# bridge.net
KiCad netlist of a schematic drawn in EAGLE
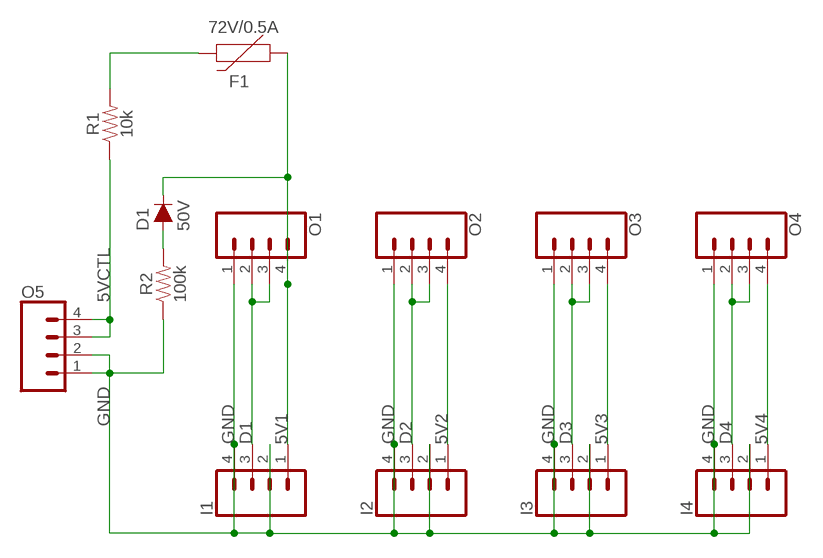
[diagram p0: schematic, sheet 1]

(export (version "E")
  (design (tool "Eeschema 10.0.6"))
  (components
    (comp (ref "D1")
      (value "50V")
      (footprint "eagle-import:DIODE-1N4001")
      (libsource (lib "eagle-import") (part "DIODE-PTH"))
    )
    (comp (ref "F1")
      (value "72V/0.5A")
      (footprint "eagle-import:PTH")
      (libsource (lib "eagle-import") (part "PPTC_PTH"))
    )
    (comp (ref "I1")
      (value "CONN_04SCREW")
      (footprint "eagle-import:SCREWTERMINAL-3.5MM-4")
      (libsource (lib "eagle-import") (part "CONN_04SCREW"))
    )
    (comp (ref "I2")
      (value "CONN_04SCREW")
      (footprint "eagle-import:SCREWTERMINAL-3.5MM-4")
      (libsource (lib "eagle-import") (part "CONN_04SCREW"))
    )
    (comp (ref "I3")
      (value "CONN_04SCREW")
      (footprint "eagle-import:SCREWTERMINAL-3.5MM-4")
      (libsource (lib "eagle-import") (part "CONN_04SCREW"))
    )
    (comp (ref "I4")
      (value "CONN_04SCREW")
      (footprint "eagle-import:SCREWTERMINAL-3.5MM-4")
      (libsource (lib "eagle-import") (part "CONN_04SCREW"))
    )
    (comp (ref "O1")
      (value "CONN_04SCREW")
      (footprint "eagle-import:SCREWTERMINAL-3.5MM-4")
      (libsource (lib "eagle-import") (part "CONN_04SCREW"))
    )
    (comp (ref "O2")
      (value "CONN_04SCREW")
      (footprint "eagle-import:SCREWTERMINAL-3.5MM-4")
      (libsource (lib "eagle-import") (part "CONN_04SCREW"))
    )
    (comp (ref "O3")
      (value "CONN_04SCREW")
      (footprint "eagle-import:SCREWTERMINAL-3.5MM-4")
      (libsource (lib "eagle-import") (part "CONN_04SCREW"))
    )
    (comp (ref "O4")
      (value "CONN_04SCREW")
      (footprint "eagle-import:SCREWTERMINAL-3.5MM-4")
      (libsource (lib "eagle-import") (part "CONN_04SCREW"))
    )
    (comp (ref "O5")
      (value "CONN_04SCREW")
      (footprint "eagle-import:SCREWTERMINAL-3.5MM-4")
      (libsource (lib "eagle-import") (part "CONN_04SCREW"))
    )
    (comp (ref "R1")
      (value "10k")
      (footprint "eagle-import:AXIAL-0.3")
      (libsource (lib "eagle-import") (part "10KOHM-HORIZ-1/4W-1%"))
    )
    (comp (ref "R2")
      (value "100k")
      (footprint "eagle-import:AXIAL-0.3")
      (libsource (lib "eagle-import") (part "100KOHM-HORIZ-1/4W-1%"))
    )
  )
  (nets
    (net (code "1") (name "/5V1") (class "Default")
      (node (ref "D1") (pin "C") (pinfunction "C_C") (pintype "passive"))
      (node (ref "F1") (pin "P$1") (pinfunction "1_P$1") (pintype "bidirectional"))
      (node (ref "I1") (pin "1") (pinfunction "1_1") (pintype "passive"))
      (node (ref "O1") (pin "4") (pinfunction "4_4") (pintype "passive"))
    )
    (net (code "2") (name "/5V2") (class "Default")
      (node (ref "I2") (pin "1") (pinfunction "1_1") (pintype "passive"))
      (node (ref "O2") (pin "4") (pinfunction "4_4") (pintype "passive"))
    )
    (net (code "3") (name "/5V3") (class "Default")
      (node (ref "I3") (pin "1") (pinfunction "1_1") (pintype "passive"))
      (node (ref "O3") (pin "4") (pinfunction "4_4") (pintype "passive"))
    )
    (net (code "4") (name "/5V4") (class "Default")
      (node (ref "I4") (pin "1") (pinfunction "1_1") (pintype "passive"))
      (node (ref "O4") (pin "4") (pinfunction "4_4") (pintype "passive"))
    )
    (net (code "5") (name "/5VCTL") (class "Default")
      (node (ref "O5") (pin "3") (pinfunction "3_3") (pintype "passive"))
      (node (ref "O5") (pin "4") (pinfunction "4_4") (pintype "passive"))
      (node (ref "R1") (pin "P$1") (pinfunction "1_P$1") (pintype "passive"))
    )
    (net (code "6") (name "/D1") (class "Default")
      (node (ref "I1") (pin "3") (pinfunction "3_3") (pintype "passive"))
      (node (ref "O1") (pin "2") (pinfunction "2_2") (pintype "passive"))
      (node (ref "O1") (pin "3") (pinfunction "3_3") (pintype "passive"))
    )
    (net (code "7") (name "/D2") (class "Default")
      (node (ref "I2") (pin "3") (pinfunction "3_3") (pintype "passive"))
      (node (ref "O2") (pin "2") (pinfunction "2_2") (pintype "passive"))
      (node (ref "O2") (pin "3") (pinfunction "3_3") (pintype "passive"))
    )
    (net (code "8") (name "/D3") (class "Default")
      (node (ref "I3") (pin "3") (pinfunction "3_3") (pintype "passive"))
      (node (ref "O3") (pin "2") (pinfunction "2_2") (pintype "passive"))
      (node (ref "O3") (pin "3") (pinfunction "3_3") (pintype "passive"))
    )
    (net (code "9") (name "/D4") (class "Default")
      (node (ref "I4") (pin "3") (pinfunction "3_3") (pintype "passive"))
      (node (ref "O4") (pin "2") (pinfunction "2_2") (pintype "passive"))
      (node (ref "O4") (pin "3") (pinfunction "3_3") (pintype "passive"))
    )
    (net (code "10") (name "/GND") (class "Default")
      (node (ref "I1") (pin "2") (pinfunction "2_2") (pintype "passive"))
      (node (ref "I1") (pin "4") (pinfunction "4_4") (pintype "passive"))
      (node (ref "I2") (pin "2") (pinfunction "2_2") (pintype "passive"))
      (node (ref "I2") (pin "4") (pinfunction "4_4") (pintype "passive"))
      (node (ref "I3") (pin "2") (pinfunction "2_2") (pintype "passive"))
      (node (ref "I3") (pin "4") (pinfunction "4_4") (pintype "passive"))
      (node (ref "I4") (pin "2") (pinfunction "2_2") (pintype "passive"))
      (node (ref "I4") (pin "4") (pinfunction "4_4") (pintype "passive"))
      (node (ref "O1") (pin "1") (pinfunction "1_1") (pintype "passive"))
      (node (ref "O2") (pin "1") (pinfunction "1_1") (pintype "passive"))
      (node (ref "O3") (pin "1") (pinfunction "1_1") (pintype "passive"))
      (node (ref "O4") (pin "1") (pinfunction "1_1") (pintype "passive"))
      (node (ref "O5") (pin "1") (pinfunction "1_1") (pintype "passive"))
      (node (ref "O5") (pin "2") (pinfunction "2_2") (pintype "passive"))
      (node (ref "R2") (pin "P$1") (pinfunction "1_P$1") (pintype "passive"))
    )
    (net (code "11") (name "Net-(F1-2)") (class "Default")
      (node (ref "F1") (pin "P$2") (pinfunction "2_P$2") (pintype "bidirectional"))
      (node (ref "R1") (pin "P$2") (pinfunction "2_P$2") (pintype "passive"))
    )
    (net (code "12") (name "Net-(R2-2)") (class "Default")
      (node (ref "D1") (pin "A") (pinfunction "A_A") (pintype "passive"))
      (node (ref "R2") (pin "P$2") (pinfunction "2_P$2") (pintype "passive"))
    )
  )
)
